# wind_direction_sensor.net
KiCad netlist of a schematic drawn in EAGLE
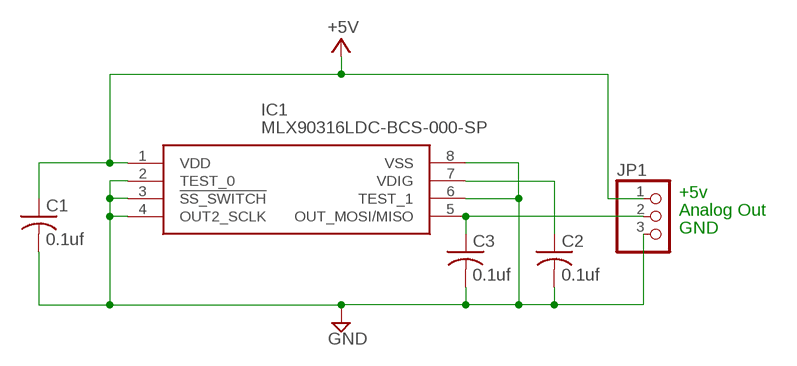
[diagram p0: schematic, sheet 1]

(export (version "E")
  (design (tool "Eeschema 10.0.6"))
  (components
    (comp (ref "C1")
      (value "0.1uf")
      (footprint "eagle-import:C1206K")
      (libsource (lib "eagle-import") (part "C-USC1206K"))
    )
    (comp (ref "C2")
      (value "0.1uf")
      (footprint "eagle-import:C1206K")
      (libsource (lib "eagle-import") (part "C-USC1206K"))
    )
    (comp (ref "C3")
      (value "0.1uf")
      (footprint "eagle-import:C1206K")
      (libsource (lib "eagle-import") (part "C-USC1206K"))
    )
    (comp (ref "IC1")
      (value "MLX90316LDC-BCS-000-SP")
      (footprint "eagle-import:SOIC127P600X172-8N")
      (fields (field (name "MOUSER_PART_NUMBER") "482-90316LDCBCS000SP"))
      (libsource (lib "eagle-import") (part "MLX90316LDC-BCS-000-SP"))
    )
    (comp (ref "JP1")
      (value "PINHD-1X3")
      (footprint "eagle-import:1X03")
      (libsource (lib "eagle-import") (part "PINHD-1X3"))
    )
  )
  (nets
    (net (code "1") (name "+5V") (class "Default")
      (node (ref "C1") (pin "1") (pinfunction "1_1") (pintype "passive"))
      (node (ref "IC1") (pin "1") (pinfunction "VDD_1") (pintype "bidirectional"))
      (node (ref "JP1") (pin "1") (pinfunction "1_1") (pintype "passive"))
    )
    (net (code "2") (name "GND") (class "Default")
      (node (ref "C1") (pin "2") (pinfunction "2_2") (pintype "passive"))
      (node (ref "C2") (pin "2") (pinfunction "2_2") (pintype "passive"))
      (node (ref "C3") (pin "2") (pinfunction "2_2") (pintype "passive"))
      (node (ref "IC1") (pin "2") (pinfunction "TEST_0_2") (pintype "bidirectional"))
      (node (ref "IC1") (pin "3") (pinfunction "~{SS_SWITCH}_3") (pintype "bidirectional"))
      (node (ref "IC1") (pin "4") (pinfunction "OUT2_SCLK_4") (pintype "bidirectional"))
      (node (ref "IC1") (pin "6") (pinfunction "TEST_1_6") (pintype "bidirectional"))
      (node (ref "IC1") (pin "8") (pinfunction "VSS_8") (pintype "bidirectional"))
      (node (ref "JP1") (pin "3") (pinfunction "3_3") (pintype "passive"))
    )
    (net (code "3") (name "Net-(IC1-OUT_MOSI{slash}MISO)") (class "Default")
      (node (ref "C3") (pin "1") (pinfunction "1_1") (pintype "passive"))
      (node (ref "IC1") (pin "5") (pinfunction "OUT_MOSI/MISO_5") (pintype "bidirectional"))
      (node (ref "JP1") (pin "2") (pinfunction "2_2") (pintype "passive"))
    )
    (net (code "4") (name "Net-(IC1-VDIG)") (class "Default")
      (node (ref "C2") (pin "1") (pinfunction "1_1") (pintype "passive"))
      (node (ref "IC1") (pin "7") (pinfunction "VDIG_7") (pintype "bidirectional"))
    )
  )
)
